# Adafruit_50pin_to_40pin_TFT_with_AR1100_.net
KiCad netlist of a schematic drawn in EAGLE
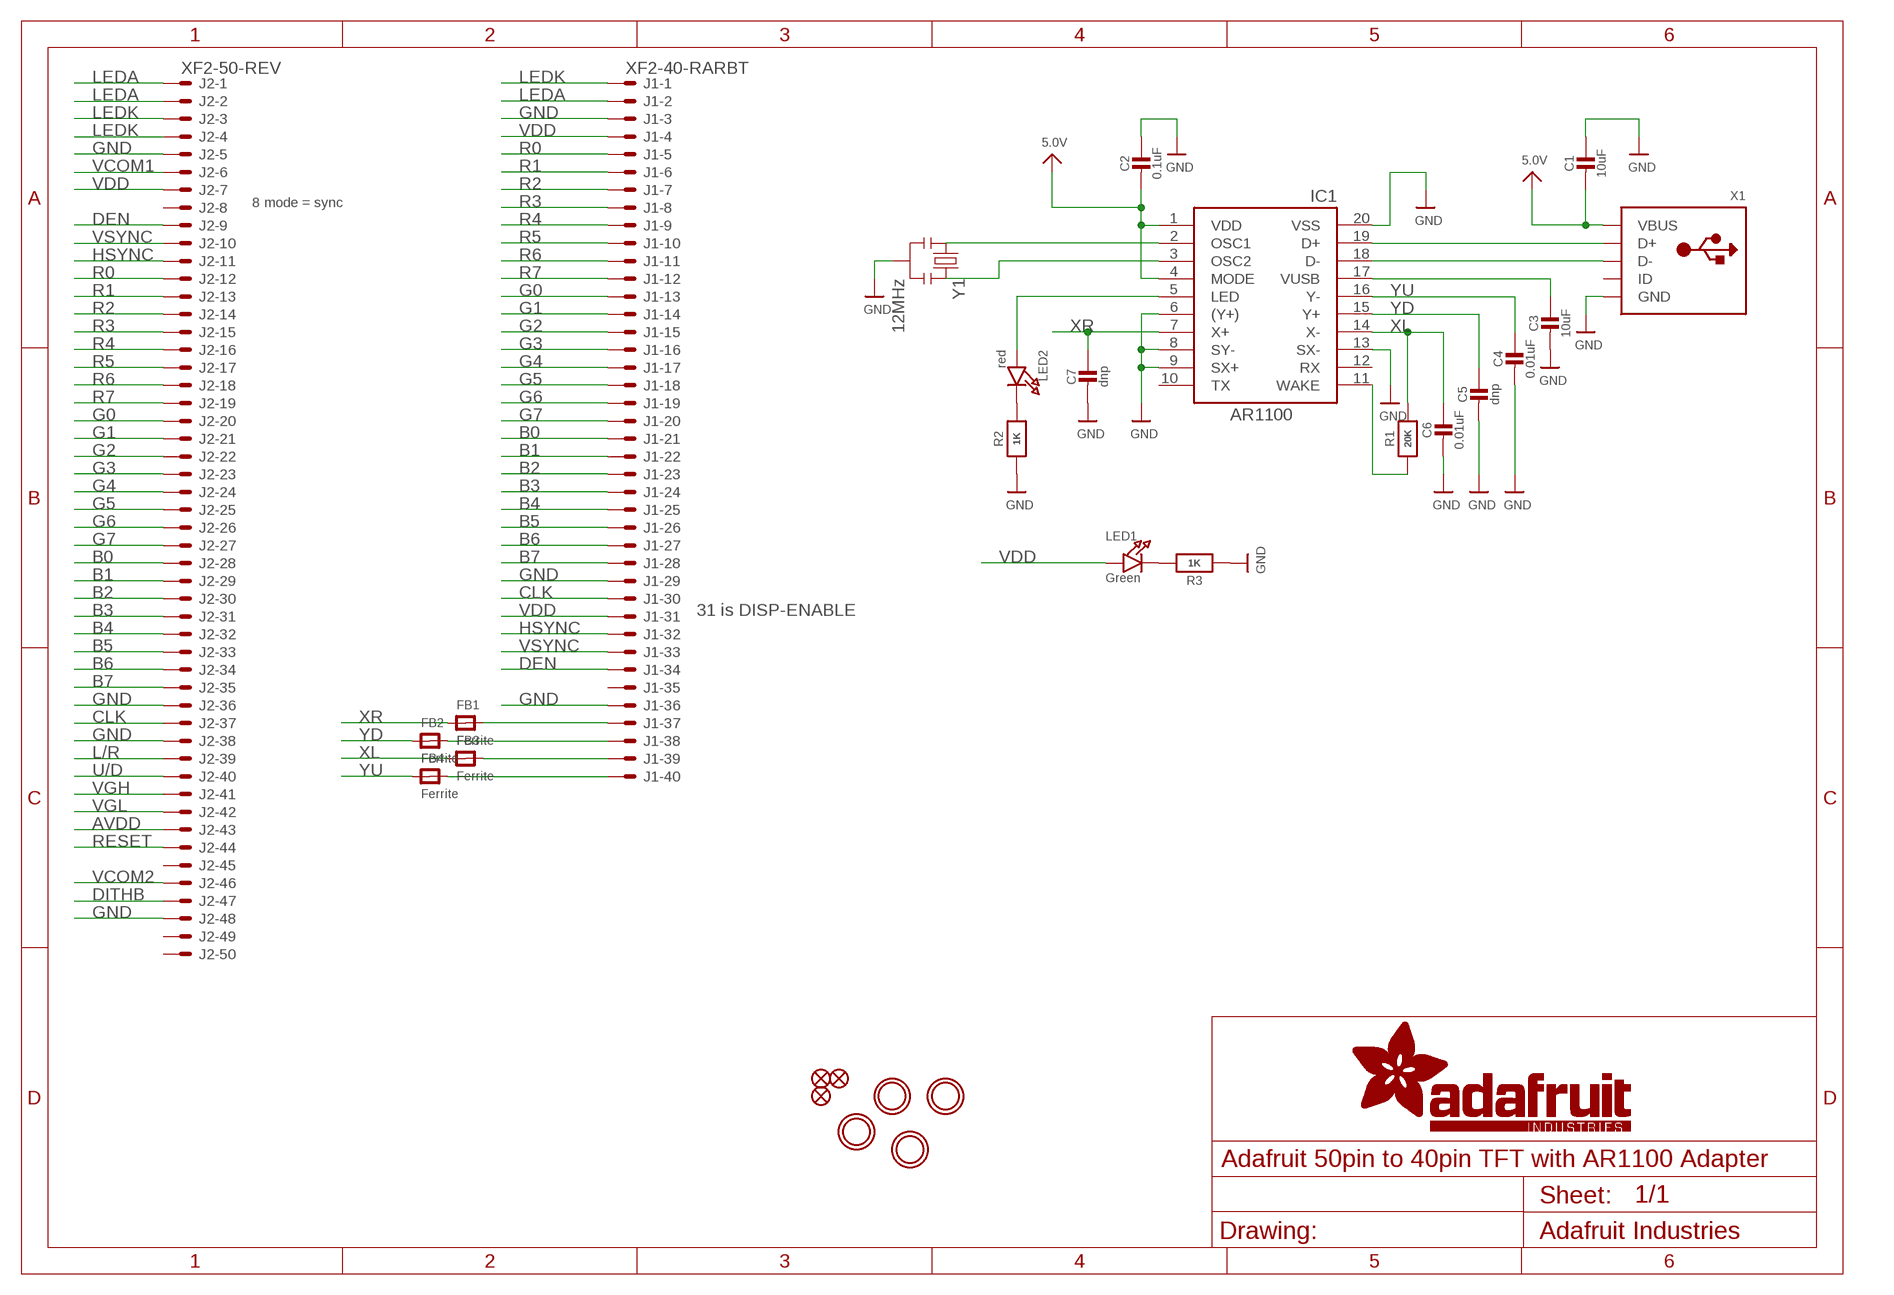
[diagram p0: schematic, sheet 1]

(export (version "E")
  (design (tool "Eeschema 10.0.6"))
  (components
    (comp (ref "C1")
      (value "10uF")
      (footprint "eagle-import:_0805MP")
      (libsource (lib "eagle-import") (part "CAP_CERAMIC_0805MP"))
    )
    (comp (ref "C2")
      (value "0.1uF")
      (footprint "eagle-import:_0805MP")
      (libsource (lib "eagle-import") (part "CAP_CERAMIC_0805MP"))
    )
    (comp (ref "C3")
      (value "10uF")
      (footprint "eagle-import:_0805MP")
      (libsource (lib "eagle-import") (part "CAP_CERAMIC_0805MP"))
    )
    (comp (ref "C4")
      (value "0.01uF")
      (footprint "eagle-import:_0805MP")
      (libsource (lib "eagle-import") (part "CAP_CERAMIC_0805MP"))
    )
    (comp (ref "C5")
      (value "dnp")
      (footprint "eagle-import:_0805MP")
      (libsource (lib "eagle-import") (part "CAP_CERAMIC_0805MP"))
    )
    (comp (ref "C6")
      (value "0.01uF")
      (footprint "eagle-import:_0805MP")
      (libsource (lib "eagle-import") (part "CAP_CERAMIC_0805MP"))
    )
    (comp (ref "C7")
      (value "dnp")
      (footprint "eagle-import:_0805MP")
      (libsource (lib "eagle-import") (part "CAP_CERAMIC_0805MP"))
    )
    (comp (ref "FB1")
      (value "Ferrite")
      (footprint "eagle-import:_0805")
      (libsource (lib "eagle-import") (part "FERRITE_0805"))
    )
    (comp (ref "FB2")
      (value "Ferrite")
      (footprint "eagle-import:_0805")
      (libsource (lib "eagle-import") (part "FERRITE_0805"))
    )
    (comp (ref "FB3")
      (value "Ferrite")
      (footprint "eagle-import:_0805")
      (libsource (lib "eagle-import") (part "FERRITE_0805"))
    )
    (comp (ref "FB4")
      (value "Ferrite")
      (footprint "eagle-import:_0805")
      (libsource (lib "eagle-import") (part "FERRITE_0805"))
    )
    (comp (ref "FID1")
      (value "FIDUCIAL\"\"")
      (footprint "eagle-import:FIDUCIAL_1MM")
      (libsource (lib "eagle-import") (part "FIDUCIAL{dblquote}{dblquote}"))
    )
    (comp (ref "FID2")
      (value "FIDUCIAL\"\"")
      (footprint "eagle-import:FIDUCIAL_1MM")
      (libsource (lib "eagle-import") (part "FIDUCIAL{dblquote}{dblquote}"))
    )
    (comp (ref "FID3")
      (value "FIDUCIAL\"\"")
      (footprint "eagle-import:FIDUCIAL_1MM")
      (libsource (lib "eagle-import") (part "FIDUCIAL{dblquote}{dblquote}"))
    )
    (comp (ref "IC1")
      (value "AR1100_SSOP")
      (footprint "eagle-import:TSSOP20-5.3MMBODY")
      (libsource (lib "eagle-import") (part "AR1100_SSOP"))
    )
    (comp (ref "J1")
      (value "XF2-40-RARBT")
      (footprint "eagle-import:4-1734839-0")
      (libsource (lib "eagle-import") (part "XF2-40?-RARBT"))
    )
    (comp (ref "J2")
      (value "XF2-50-REV")
      (footprint "eagle-import:5-1734839-0-REV")
      (libsource (lib "eagle-import") (part "XF2-50?-REV"))
    )
    (comp (ref "LED1")
      (value "Green")
      (footprint "eagle-import:CHIPLED_0805_NOOUTLINE")
      (libsource (lib "eagle-import") (part "LED0805_NOOUTLINE"))
    )
    (comp (ref "LED2")
      (value "red")
      (footprint "eagle-import:CHIPLED_0805_NOOUTLINE")
      (libsource (lib "eagle-import") (part "LED0805_NOOUTLINE"))
    )
    (comp (ref "R1")
      (value "20K")
      (footprint "eagle-import:_0805MP")
      (libsource (lib "eagle-import") (part "RESISTOR_0805MP"))
    )
    (comp (ref "R2")
      (value "1K")
      (footprint "eagle-import:_0805MP")
      (libsource (lib "eagle-import") (part "RESISTOR_0805MP"))
    )
    (comp (ref "R3")
      (value "1K")
      (footprint "eagle-import:_0805MP")
      (libsource (lib "eagle-import") (part "RESISTOR_0805MP"))
    )
    (comp (ref "U$11")
      (value "MOUNTINGHOLE2.5")
      (footprint "eagle-import:MOUNTINGHOLE_2.5_PLATED")
      (libsource (lib "eagle-import") (part "MOUNTINGHOLE2.5"))
    )
    (comp (ref "U$14")
      (value "MOUNTINGHOLE2.5")
      (footprint "eagle-import:MOUNTINGHOLE_2.5_PLATED")
      (libsource (lib "eagle-import") (part "MOUNTINGHOLE2.5"))
    )
    (comp (ref "U$15")
      (value "MOUNTINGHOLE2.5")
      (footprint "eagle-import:MOUNTINGHOLE_2.5_PLATED")
      (libsource (lib "eagle-import") (part "MOUNTINGHOLE2.5"))
    )
    (comp (ref "U$16")
      (value "MOUNTINGHOLE2.5")
      (footprint "eagle-import:MOUNTINGHOLE_2.5_PLATED")
      (libsource (lib "eagle-import") (part "MOUNTINGHOLE2.5"))
    )
    (comp (ref "X1")
      (value "USBMINIBLARGE")
      (footprint "eagle-import:USB-MINIB_LARGER")
      (libsource (lib "eagle-import") (part "USBMINIBLARGE"))
    )
    (comp (ref "Y1")
      (value "12MHz")
      (footprint "eagle-import:RESONATOR-SMD")
      (libsource (lib "eagle-import") (part "RESONATORSMD"))
    )
  )
  (nets
    (net (code "1") (name "/AVDD") (class "Default")
      (node (ref "J2") (pin "43") (pinfunction "MS_43") (pintype "passive"))
    )
    (net (code "2") (name "/B0") (class "Default")
      (node (ref "J1") (pin "21") (pinfunction "MS_21") (pintype "passive"))
      (node (ref "J2") (pin "28") (pinfunction "MS_28") (pintype "passive"))
    )
    (net (code "3") (name "/B1") (class "Default")
      (node (ref "J1") (pin "22") (pinfunction "MS_22") (pintype "passive"))
      (node (ref "J2") (pin "29") (pinfunction "MS_29") (pintype "passive"))
    )
    (net (code "4") (name "/B2") (class "Default")
      (node (ref "J1") (pin "23") (pinfunction "MS_23") (pintype "passive"))
      (node (ref "J2") (pin "30") (pinfunction "MS_30") (pintype "passive"))
    )
    (net (code "5") (name "/B3") (class "Default")
      (node (ref "J1") (pin "24") (pinfunction "MS_24") (pintype "passive"))
      (node (ref "J2") (pin "31") (pinfunction "MS_31") (pintype "passive"))
    )
    (net (code "6") (name "/B4") (class "Default")
      (node (ref "J1") (pin "25") (pinfunction "MS_25") (pintype "passive"))
      (node (ref "J2") (pin "32") (pinfunction "MS_32") (pintype "passive"))
    )
    (net (code "7") (name "/B5") (class "Default")
      (node (ref "J1") (pin "26") (pinfunction "MS_26") (pintype "passive"))
      (node (ref "J2") (pin "33") (pinfunction "MS_33") (pintype "passive"))
    )
    (net (code "8") (name "/B6") (class "Default")
      (node (ref "J1") (pin "27") (pinfunction "MS_27") (pintype "passive"))
      (node (ref "J2") (pin "34") (pinfunction "MS_34") (pintype "passive"))
    )
    (net (code "9") (name "/B7") (class "Default")
      (node (ref "J1") (pin "28") (pinfunction "MS_28") (pintype "passive"))
      (node (ref "J2") (pin "35") (pinfunction "MS_35") (pintype "passive"))
    )
    (net (code "10") (name "/CLK") (class "Default")
      (node (ref "J1") (pin "30") (pinfunction "MS_30") (pintype "passive"))
      (node (ref "J2") (pin "37") (pinfunction "MS_37") (pintype "passive"))
    )
    (net (code "11") (name "/DEN") (class "Default")
      (node (ref "J1") (pin "34") (pinfunction "MS_34") (pintype "passive"))
      (node (ref "J2") (pin "9") (pinfunction "MS_9") (pintype "passive"))
    )
    (net (code "12") (name "/DITHB") (class "Default")
      (node (ref "J2") (pin "47") (pinfunction "MS_47") (pintype "passive"))
    )
    (net (code "13") (name "/G0") (class "Default")
      (node (ref "J1") (pin "13") (pinfunction "MS_13") (pintype "passive"))
      (node (ref "J2") (pin "20") (pinfunction "MS_20") (pintype "passive"))
    )
    (net (code "14") (name "/G1") (class "Default")
      (node (ref "J1") (pin "14") (pinfunction "MS_14") (pintype "passive"))
      (node (ref "J2") (pin "21") (pinfunction "MS_21") (pintype "passive"))
    )
    (net (code "15") (name "/G2") (class "Default")
      (node (ref "J1") (pin "15") (pinfunction "MS_15") (pintype "passive"))
      (node (ref "J2") (pin "22") (pinfunction "MS_22") (pintype "passive"))
    )
    (net (code "16") (name "/G3") (class "Default")
      (node (ref "J1") (pin "16") (pinfunction "MS_16") (pintype "passive"))
      (node (ref "J2") (pin "23") (pinfunction "MS_23") (pintype "passive"))
    )
    (net (code "17") (name "/G4") (class "Default")
      (node (ref "J1") (pin "17") (pinfunction "MS_17") (pintype "passive"))
      (node (ref "J2") (pin "24") (pinfunction "MS_24") (pintype "passive"))
    )
    (net (code "18") (name "/G5") (class "Default")
      (node (ref "J1") (pin "18") (pinfunction "MS_18") (pintype "passive"))
      (node (ref "J2") (pin "25") (pinfunction "MS_25") (pintype "passive"))
    )
    (net (code "19") (name "/G6") (class "Default")
      (node (ref "J1") (pin "19") (pinfunction "MS_19") (pintype "passive"))
      (node (ref "J2") (pin "26") (pinfunction "MS_26") (pintype "passive"))
    )
    (net (code "20") (name "/G7") (class "Default")
      (node (ref "J1") (pin "20") (pinfunction "MS_20") (pintype "passive"))
      (node (ref "J2") (pin "27") (pinfunction "MS_27") (pintype "passive"))
    )
    (net (code "21") (name "/HSYNC") (class "Default")
      (node (ref "J1") (pin "32") (pinfunction "MS_32") (pintype "passive"))
      (node (ref "J2") (pin "11") (pinfunction "MS_11") (pintype "passive"))
    )
    (net (code "22") (name "/LEDA") (class "Default")
      (node (ref "J1") (pin "2") (pinfunction "MS_2") (pintype "passive"))
      (node (ref "J2") (pin "1") (pinfunction "MSV_1") (pintype "passive"))
      (node (ref "J2") (pin "2") (pinfunction "MS_2") (pintype "passive"))
    )
    (net (code "23") (name "/LEDK") (class "Default")
      (node (ref "J1") (pin "1") (pinfunction "MSV_1") (pintype "passive"))
      (node (ref "J2") (pin "3") (pinfunction "MS_3") (pintype "passive"))
      (node (ref "J2") (pin "4") (pinfunction "MS_4") (pintype "passive"))
    )
    (net (code "24") (name "/L{slash}R") (class "Default")
      (node (ref "J2") (pin "39") (pinfunction "MS_39") (pintype "passive"))
    )
    (net (code "25") (name "/R0") (class "Default")
      (node (ref "J1") (pin "5") (pinfunction "MS_5") (pintype "passive"))
      (node (ref "J2") (pin "12") (pinfunction "MS_12") (pintype "passive"))
    )
    (net (code "26") (name "/R1") (class "Default")
      (node (ref "J1") (pin "6") (pinfunction "MS_6") (pintype "passive"))
      (node (ref "J2") (pin "13") (pinfunction "MS_13") (pintype "passive"))
    )
    (net (code "27") (name "/R2") (class "Default")
      (node (ref "J1") (pin "7") (pinfunction "MS_7") (pintype "passive"))
      (node (ref "J2") (pin "14") (pinfunction "MS_14") (pintype "passive"))
    )
    (net (code "28") (name "/R3") (class "Default")
      (node (ref "J1") (pin "8") (pinfunction "MS_8") (pintype "passive"))
      (node (ref "J2") (pin "15") (pinfunction "MS_15") (pintype "passive"))
    )
    (net (code "29") (name "/R4") (class "Default")
      (node (ref "J1") (pin "9") (pinfunction "MS_9") (pintype "passive"))
      (node (ref "J2") (pin "16") (pinfunction "MS_16") (pintype "passive"))
    )
    (net (code "30") (name "/R5") (class "Default")
      (node (ref "J1") (pin "10") (pinfunction "MS_10") (pintype "passive"))
      (node (ref "J2") (pin "17") (pinfunction "MS_17") (pintype "passive"))
    )
    (net (code "31") (name "/R6") (class "Default")
      (node (ref "J1") (pin "11") (pinfunction "MS_11") (pintype "passive"))
      (node (ref "J2") (pin "18") (pinfunction "MS_18") (pintype "passive"))
    )
    (net (code "32") (name "/R7") (class "Default")
      (node (ref "J1") (pin "12") (pinfunction "MS_12") (pintype "passive"))
      (node (ref "J2") (pin "19") (pinfunction "MS_19") (pintype "passive"))
    )
    (net (code "33") (name "/RESET") (class "Default")
      (node (ref "J2") (pin "44") (pinfunction "MS_44") (pintype "passive"))
    )
    (net (code "34") (name "/U{slash}D") (class "Default")
      (node (ref "J2") (pin "40") (pinfunction "MS_40") (pintype "passive"))
    )
    (net (code "35") (name "/VCOM1") (class "Default")
      (node (ref "J2") (pin "6") (pinfunction "MS_6") (pintype "passive"))
    )
    (net (code "36") (name "/VCOM2") (class "Default")
      (node (ref "J2") (pin "46") (pinfunction "MS_46") (pintype "passive"))
    )
    (net (code "37") (name "/VDD") (class "Default")
      (node (ref "J1") (pin "31") (pinfunction "MS_31") (pintype "passive"))
      (node (ref "J1") (pin "4") (pinfunction "MS_4") (pintype "passive"))
      (node (ref "J2") (pin "7") (pinfunction "MS_7") (pintype "passive"))
      (node (ref "LED1") (pin "A") (pinfunction "A_A") (pintype "passive"))
    )
    (net (code "38") (name "/VGH") (class "Default")
      (node (ref "J2") (pin "41") (pinfunction "MS_41") (pintype "passive"))
    )
    (net (code "39") (name "/VGL") (class "Default")
      (node (ref "J2") (pin "42") (pinfunction "MS_42") (pintype "passive"))
    )
    (net (code "40") (name "/VSYNC") (class "Default")
      (node (ref "J1") (pin "33") (pinfunction "MS_33") (pintype "passive"))
      (node (ref "J2") (pin "10") (pinfunction "MS_10") (pintype "passive"))
    )
    (net (code "41") (name "/XL") (class "Default")
      (node (ref "C6") (pin "1") (pinfunction "1_1") (pintype "passive"))
      (node (ref "FB3") (pin "1") (pinfunction "P$1_1") (pintype "passive"))
      (node (ref "IC1") (pin "14") (pinfunction "X-_14") (pintype "bidirectional"))
      (node (ref "R1") (pin "2") (pinfunction "2_2") (pintype "passive"))
    )
    (net (code "42") (name "/XR") (class "Default")
      (node (ref "C7") (pin "1") (pinfunction "1_1") (pintype "passive"))
      (node (ref "FB1") (pin "1") (pinfunction "P$1_1") (pintype "passive"))
      (node (ref "IC1") (pin "7") (pinfunction "X+_7") (pintype "bidirectional"))
    )
    (net (code "43") (name "/YD") (class "Default")
      (node (ref "C5") (pin "1") (pinfunction "1_1") (pintype "passive"))
      (node (ref "FB2") (pin "1") (pinfunction "P$1_1") (pintype "passive"))
      (node (ref "IC1") (pin "15") (pinfunction "Y+_15") (pintype "bidirectional"))
    )
    (net (code "44") (name "/YU") (class "Default")
      (node (ref "C4") (pin "1") (pinfunction "1_1") (pintype "passive"))
      (node (ref "FB4") (pin "1") (pinfunction "P$1_1") (pintype "passive"))
      (node (ref "IC1") (pin "16") (pinfunction "Y-_16") (pintype "bidirectional"))
    )
    (net (code "45") (name "5.0V") (class "Default")
      (node (ref "C1") (pin "2") (pinfunction "2_2") (pintype "passive"))
      (node (ref "C2") (pin "2") (pinfunction "2_2") (pintype "passive"))
      (node (ref "IC1") (pin "1") (pinfunction "VDD_1") (pintype "power_in"))
      (node (ref "IC1") (pin "4") (pinfunction "MODE_4") (pintype "input"))
      (node (ref "X1") (pin "VBUS") (pinfunction "VBUS_VBUS") (pintype "power_in"))
    )
    (net (code "46") (name "GND") (class "Default")
      (node (ref "C1") (pin "1") (pinfunction "1_1") (pintype "passive"))
      (node (ref "C2") (pin "1") (pinfunction "1_1") (pintype "passive"))
      (node (ref "C3") (pin "2") (pinfunction "2_2") (pintype "passive"))
      (node (ref "C4") (pin "2") (pinfunction "2_2") (pintype "passive"))
      (node (ref "C5") (pin "2") (pinfunction "2_2") (pintype "passive"))
      (node (ref "C6") (pin "2") (pinfunction "2_2") (pintype "passive"))
      (node (ref "C7") (pin "2") (pinfunction "2_2") (pintype "passive"))
      (node (ref "IC1") (pin "13") (pinfunction "SX-_13") (pintype "bidirectional"))
      (node (ref "IC1") (pin "20") (pinfunction "VSS_20") (pintype "power_in"))
      (node (ref "IC1") (pin "6") (pinfunction "(Y+)_6") (pintype "bidirectional"))
      (node (ref "IC1") (pin "8") (pinfunction "SY-_8") (pintype "bidirectional"))
      (node (ref "IC1") (pin "9") (pinfunction "SX+_9") (pintype "bidirectional"))
      (node (ref "J1") (pin "29") (pinfunction "MS_29") (pintype "passive"))
      (node (ref "J1") (pin "3") (pinfunction "MS_3") (pintype "passive"))
      (node (ref "J1") (pin "36") (pinfunction "MS_36") (pintype "passive"))
      (node (ref "J2") (pin "36") (pinfunction "MS_36") (pintype "passive"))
      (node (ref "J2") (pin "38") (pinfunction "MS_38") (pintype "passive"))
      (node (ref "J2") (pin "48") (pinfunction "MS_48") (pintype "passive"))
      (node (ref "J2") (pin "5") (pinfunction "MS_5") (pintype "passive"))
      (node (ref "R2") (pin "1") (pinfunction "1_1") (pintype "passive"))
      (node (ref "R3") (pin "1") (pinfunction "1_1") (pintype "passive"))
      (node (ref "X1") (pin "GND") (pinfunction "GND_GND") (pintype "power_in"))
      (node (ref "X1") (pin "GND1") (pinfunction "GND_GND1") (pintype "power_in"))
      (node (ref "X1") (pin "GND2") (pinfunction "GND_GND2") (pintype "power_in"))
      (node (ref "X1") (pin "GND3") (pinfunction "GND_GND3") (pintype "power_in"))
      (node (ref "X1") (pin "GND4") (pinfunction "GND_GND4") (pintype "power_in"))
      (node (ref "Y1") (pin "2") (pinfunction "2_2") (pintype "passive"))
    )
    (net (code "47") (name "Net-(FB1-P$2)") (class "Default")
      (node (ref "FB1") (pin "2") (pinfunction "P$2_2") (pintype "passive"))
      (node (ref "J1") (pin "37") (pinfunction "MS_37") (pintype "passive"))
    )
    (net (code "48") (name "Net-(FB2-P$2)") (class "Default")
      (node (ref "FB2") (pin "2") (pinfunction "P$2_2") (pintype "passive"))
      (node (ref "J1") (pin "38") (pinfunction "MS_38") (pintype "passive"))
    )
    (net (code "49") (name "Net-(FB3-P$2)") (class "Default")
      (node (ref "FB3") (pin "2") (pinfunction "P$2_2") (pintype "passive"))
      (node (ref "J1") (pin "39") (pinfunction "MS_39") (pintype "passive"))
    )
    (net (code "50") (name "Net-(FB4-P$2)") (class "Default")
      (node (ref "FB4") (pin "2") (pinfunction "P$2_2") (pintype "passive"))
      (node (ref "J1") (pin "40") (pinfunction "MS_40") (pintype "passive"))
    )
    (net (code "51") (name "Net-(IC1-D+)") (class "Default")
      (node (ref "IC1") (pin "19") (pinfunction "D+_19") (pintype "bidirectional"))
      (node (ref "X1") (pin "D+") (pinfunction "D+_D+") (pintype "bidirectional"))
    )
    (net (code "52") (name "Net-(IC1-D-)") (class "Default")
      (node (ref "IC1") (pin "18") (pinfunction "D-_18") (pintype "bidirectional"))
      (node (ref "X1") (pin "D-") (pinfunction "D-_D-") (pintype "bidirectional"))
    )
    (net (code "53") (name "Net-(IC1-LED)") (class "Default")
      (node (ref "IC1") (pin "5") (pinfunction "LED_5") (pintype "output"))
      (node (ref "LED2") (pin "A") (pinfunction "A_A") (pintype "passive"))
    )
    (net (code "54") (name "Net-(IC1-OSC1)") (class "Default")
      (node (ref "IC1") (pin "2") (pinfunction "OSC1_2") (pintype "passive"))
      (node (ref "Y1") (pin "1") (pinfunction "1_1") (pintype "passive"))
    )
    (net (code "55") (name "Net-(IC1-OSC2)") (class "Default")
      (node (ref "IC1") (pin "3") (pinfunction "OSC2_3") (pintype "passive"))
      (node (ref "Y1") (pin "3") (pinfunction "3_3") (pintype "passive"))
    )
    (net (code "56") (name "Net-(IC1-VUSB)") (class "Default")
      (node (ref "C3") (pin "1") (pinfunction "1_1") (pintype "passive"))
      (node (ref "IC1") (pin "17") (pinfunction "VUSB_17") (pintype "power_in"))
    )
    (net (code "57") (name "Net-(IC1-WAKE)") (class "Default")
      (node (ref "IC1") (pin "11") (pinfunction "WAKE_11") (pintype "input"))
      (node (ref "R1") (pin "1") (pinfunction "1_1") (pintype "passive"))
    )
    (net (code "58") (name "Net-(LED1-PadC)") (class "Default")
      (node (ref "LED1") (pin "C") (pinfunction "C_C") (pintype "passive"))
      (node (ref "R3") (pin "2") (pinfunction "2_2") (pintype "passive"))
    )
    (net (code "59") (name "Net-(LED2-PadC)") (class "Default")
      (node (ref "LED2") (pin "C") (pinfunction "C_C") (pintype "passive"))
      (node (ref "R2") (pin "2") (pinfunction "2_2") (pintype "passive"))
    )
    (net (code "60") (name "unconnected-(IC1-RX-Pad12)") (class "Default")
      (node (ref "IC1") (pin "12") (pinfunction "RX_12") (pintype "input"))
    )
    (net (code "61") (name "unconnected-(IC1-TX-Pad10)") (class "Default")
      (node (ref "IC1") (pin "10") (pinfunction "TX_10") (pintype "output"))
    )
    (net (code "62") (name "unconnected-(J1AC-MS-Pad35)") (class "Default")
      (node (ref "J1") (pin "35") (pinfunction "MS_35") (pintype "passive"))
    )
    (net (code "63") (name "unconnected-(J2AN-MS-Pad45)") (class "Default")
      (node (ref "J2") (pin "45") (pinfunction "MS_45") (pintype "passive"))
    )
    (net (code "64") (name "unconnected-(J2AR-MS-Pad49)") (class "Default")
      (node (ref "J2") (pin "49") (pinfunction "MS_49") (pintype "passive"))
    )
    (net (code "65") (name "unconnected-(J2AT-MS-Pad50)") (class "Default")
      (node (ref "J2") (pin "50") (pinfunction "MS_50") (pintype "passive"))
    )
    (net (code "66") (name "unconnected-(J2AW-MS-Pad8)") (class "Default")
      (node (ref "J2") (pin "8") (pinfunction "MS_8") (pintype "passive"))
    )
    (net (code "67") (name "unconnected-(X1-PadID)") (class "Default")
      (node (ref "X1") (pin "ID") (pinfunction "ID_ID") (pintype "bidirectional"))
    )
  )
)
